# Lightbox_schematic_27NOV.net
KiCad netlist of a schematic drawn in EAGLE
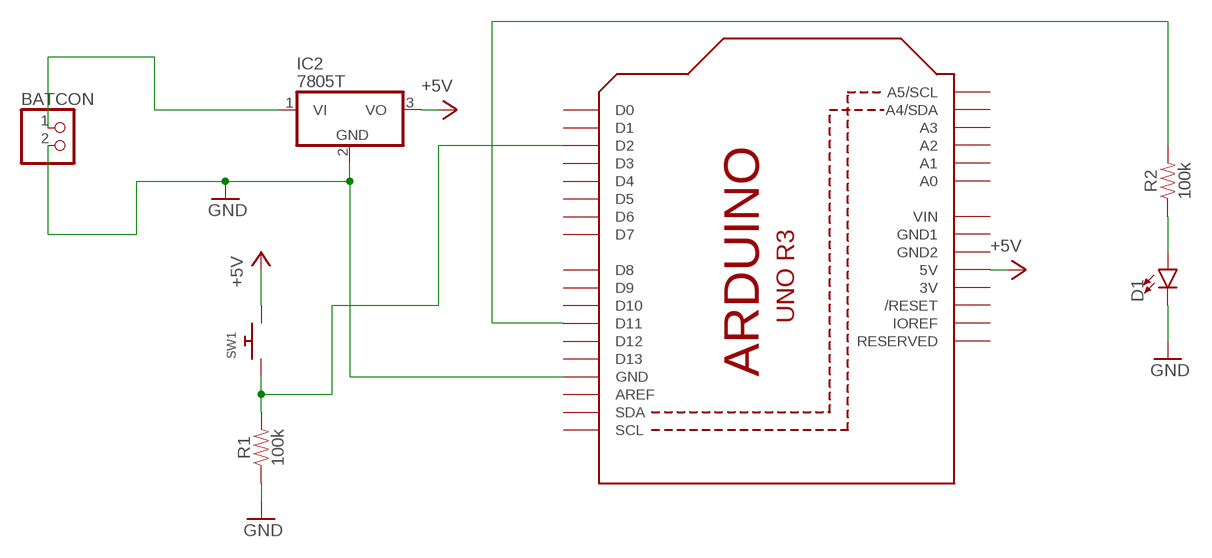
[diagram p0: schematic, sheet 1]

(export (version "E")
  (design (tool "Eeschema 10.0.6"))
  (components
    (comp (ref "BATCON")
      (value "PINHD-1X2")
      (footprint "eagle-import:1X02")
      (libsource (lib "eagle-import") (part "PINHD-1X2"))
    )
    (comp (ref "D1")
      (value "LED3MM")
      (footprint "eagle-import:LED_3MM")
      (libsource (lib "eagle-import") (part "LED3MM"))
    )
    (comp (ref "IC2")
      (value "7805T")
      (footprint "eagle-import:TO220H")
      (libsource (lib "eagle-import") (part "78T05"))
    )
    (comp (ref "R1")
      (value "100k")
      (footprint "eagle-import:AXIAL-0.3")
      (libsource (lib "eagle-import") (part "100KOHM-HORIZ-1/4W-1%"))
    )
    (comp (ref "R2")
      (value "100k")
      (footprint "eagle-import:AXIAL-0.3")
      (libsource (lib "eagle-import") (part "100KOHM-HORIZ-1/4W-1%"))
    )
    (comp (ref "SW1")
      (value "SWITCH_PUSHBUTTONSOFTTOUCHSMD_SJ")
      (footprint "eagle-import:PUSHBUTTON_SMD_SJ")
      (libsource (lib "eagle-import") (part "SWITCH_PUSHBUTTONSOFTTOUCHSMD_SJ"))
    )
    (comp (ref "U1")
      (value "ARDUINOR3-DIMENSION")
      (footprint "eagle-import:ARDUINOR3")
      (libsource (lib "eagle-import") (part "ARDUINOR3-DIMENSION"))
    )
  )
  (nets
    (net (code "1") (name "+5V") (class "Default")
      (node (ref "IC2") (pin "3") (pinfunction "VO_3") (pintype "passive"))
      (node (ref "SW1") (pin "P$2") (pinfunction "P$2_P$2") (pintype "passive"))
      (node (ref "U1") (pin "5V") (pinfunction "5V_5V") (pintype "power_in"))
    )
    (net (code "2") (name "/3V") (class "Default")
      (node (ref "U1") (pin "3V") (pinfunction "3V_3V") (pintype "power_in"))
    )
    (net (code "3") (name "/GND1") (class "Default")
      (node (ref "U1") (pin "GND1") (pinfunction "GND1_GND1") (pintype "power_in"))
    )
    (net (code "4") (name "/GND2") (class "Default")
      (node (ref "U1") (pin "GND2") (pinfunction "GND2_GND2") (pintype "power_in"))
    )
    (net (code "5") (name "/VIN") (class "Default")
      (node (ref "U1") (pin "VIN") (pinfunction "VIN_VIN") (pintype "power_in"))
    )
    (net (code "6") (name "GND") (class "Default")
      (node (ref "BATCON") (pin "2") (pinfunction "2_2") (pintype "passive"))
      (node (ref "D1") (pin "K") (pinfunction "C_K") (pintype "passive"))
      (node (ref "IC2") (pin "2") (pinfunction "GND_2") (pintype "passive"))
      (node (ref "R1") (pin "P$1") (pinfunction "1_P$1") (pintype "passive"))
      (node (ref "U1") (pin "GND") (pinfunction "GND_GND") (pintype "power_in"))
    )
    (net (code "7") (name "Net-(IC2-VI)") (class "Default")
      (node (ref "BATCON") (pin "1") (pinfunction "1_1") (pintype "passive"))
      (node (ref "IC2") (pin "1") (pinfunction "VI_1") (pintype "input"))
    )
    (net (code "8") (name "Net-(R1-2)") (class "Default")
      (node (ref "R1") (pin "P$2") (pinfunction "2_P$2") (pintype "passive"))
      (node (ref "SW1") (pin "P$1") (pinfunction "P$1_P$1") (pintype "passive"))
      (node (ref "U1") (pin "D2") (pinfunction "D2_D2") (pintype "bidirectional"))
    )
    (net (code "9") (name "Net-(R2-1)") (class "Default")
      (node (ref "D1") (pin "A") (pinfunction "A_A") (pintype "passive"))
      (node (ref "R2") (pin "P$1") (pinfunction "1_P$1") (pintype "passive"))
    )
    (net (code "10") (name "Net-(R2-2)") (class "Default")
      (node (ref "R2") (pin "P$2") (pinfunction "2_P$2") (pintype "passive"))
      (node (ref "U1") (pin "D11") (pinfunction "D11_D11") (pintype "bidirectional"))
    )
    (net (code "11") (name "unconnected-(U1-A4{slash}SDA-PadA4)") (class "Default")
      (node (ref "U1") (pin "A4") (pinfunction "A4/SDA_A4") (pintype "bidirectional"))
    )
    (net (code "12") (name "unconnected-(U1-A5{slash}SCL-PadA5)") (class "Default")
      (node (ref "U1") (pin "A5") (pinfunction "A5/SCL_A5") (pintype "bidirectional"))
    )
    (net (code "13") (name "unconnected-(U1-PadA0)") (class "Default")
      (node (ref "U1") (pin "A0") (pinfunction "A0_A0") (pintype "bidirectional"))
    )
    (net (code "14") (name "unconnected-(U1-PadA1)") (class "Default")
      (node (ref "U1") (pin "A1") (pinfunction "A1_A1") (pintype "bidirectional"))
    )
    (net (code "15") (name "unconnected-(U1-PadA2)") (class "Default")
      (node (ref "U1") (pin "A2") (pinfunction "A2_A2") (pintype "bidirectional"))
    )
    (net (code "16") (name "unconnected-(U1-PadA3)") (class "Default")
      (node (ref "U1") (pin "A3") (pinfunction "A3_A3") (pintype "bidirectional"))
    )
    (net (code "17") (name "unconnected-(U1-PadAREF)") (class "Default")
      (node (ref "U1") (pin "AREF") (pinfunction "AREF_AREF") (pintype "bidirectional"))
    )
    (net (code "18") (name "unconnected-(U1-PadD0)") (class "Default")
      (node (ref "U1") (pin "D0") (pinfunction "D0_D0") (pintype "bidirectional"))
    )
    (net (code "19") (name "unconnected-(U1-PadD1)") (class "Default")
      (node (ref "U1") (pin "D1") (pinfunction "D1_D1") (pintype "bidirectional"))
    )
    (net (code "20") (name "unconnected-(U1-PadD3)") (class "Default")
      (node (ref "U1") (pin "D3") (pinfunction "D3_D3") (pintype "bidirectional"))
    )
    (net (code "21") (name "unconnected-(U1-PadD4)") (class "Default")
      (node (ref "U1") (pin "D4") (pinfunction "D4_D4") (pintype "bidirectional"))
    )
    (net (code "22") (name "unconnected-(U1-PadD5)") (class "Default")
      (node (ref "U1") (pin "D5") (pinfunction "D5_D5") (pintype "bidirectional"))
    )
    (net (code "23") (name "unconnected-(U1-PadD6)") (class "Default")
      (node (ref "U1") (pin "D6") (pinfunction "D6_D6") (pintype "bidirectional"))
    )
    (net (code "24") (name "unconnected-(U1-PadD7)") (class "Default")
      (node (ref "U1") (pin "D7") (pinfunction "D7_D7") (pintype "bidirectional"))
    )
    (net (code "25") (name "unconnected-(U1-PadD8)") (class "Default")
      (node (ref "U1") (pin "D8") (pinfunction "D8_D8") (pintype "bidirectional"))
    )
    (net (code "26") (name "unconnected-(U1-PadD9)") (class "Default")
      (node (ref "U1") (pin "D9") (pinfunction "D9_D9") (pintype "bidirectional"))
    )
    (net (code "27") (name "unconnected-(U1-PadD10)") (class "Default")
      (node (ref "U1") (pin "D10") (pinfunction "D10_D10") (pintype "bidirectional"))
    )
    (net (code "28") (name "unconnected-(U1-PadD12)") (class "Default")
      (node (ref "U1") (pin "D12") (pinfunction "D12_D12") (pintype "bidirectional"))
    )
    (net (code "29") (name "unconnected-(U1-PadD13)") (class "Default")
      (node (ref "U1") (pin "D13") (pinfunction "D13_D13") (pintype "bidirectional"))
    )
    (net (code "30") (name "unconnected-(U1-PadIOREF)") (class "Default")
      (node (ref "U1") (pin "IOREF") (pinfunction "IOREF_IOREF") (pintype "output"))
    )
    (net (code "31") (name "unconnected-(U1-PadRESERVED)") (class "Default")
      (node (ref "U1") (pin "RESERVED") (pinfunction "RESERVED_RESERVED") (pintype "no_connect"))
    )
    (net (code "32") (name "unconnected-(U1-PadSCL)") (class "Default")
      (node (ref "U1") (pin "SCL") (pinfunction "SCL_SCL") (pintype "bidirectional"))
    )
    (net (code "33") (name "unconnected-(U1-PadSDA)") (class "Default")
      (node (ref "U1") (pin "SDA") (pinfunction "SDA_SDA") (pintype "bidirectional"))
    )
    (net (code "34") (name "unconnected-(U1-{slash}RESET-PadRESET)") (class "Default")
      (node (ref "U1") (pin "RESET") (pinfunction "/RESET_RESET") (pintype "bidirectional"))
    )
  )
)
